# Battery_Monitor_4Cell.net
KiCad netlist of a schematic drawn in Altium Designer
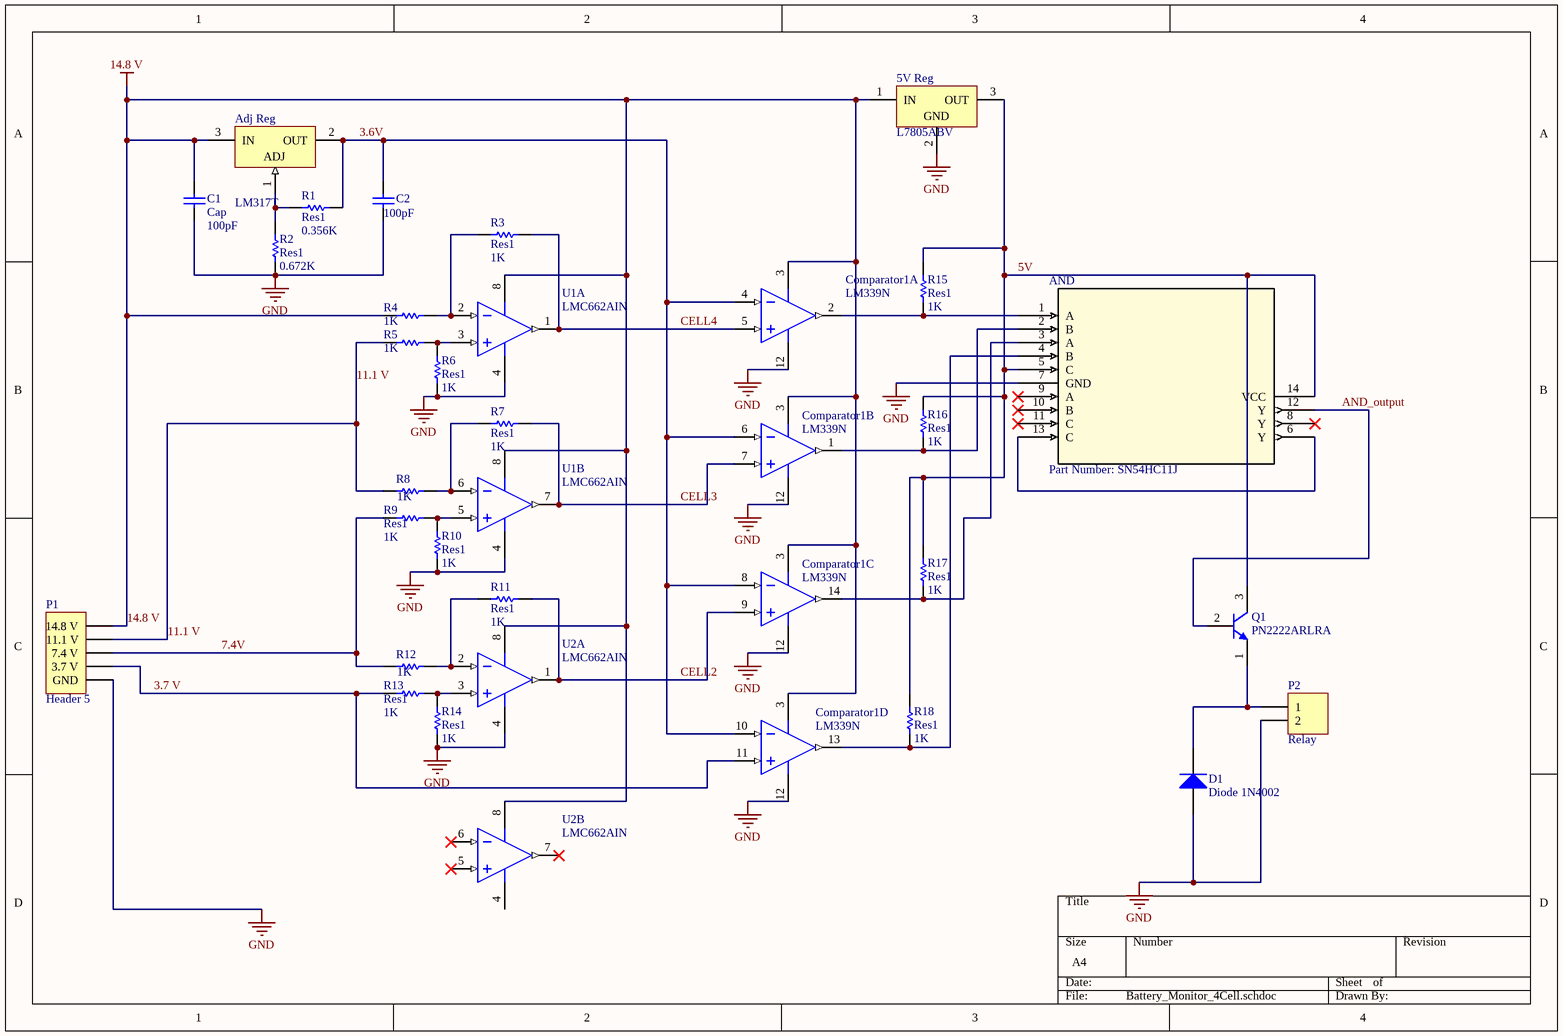
[diagram p0: Battery_Monitor_4Cell.schdoc]

(export (version "E")
  (design (tool "Eeschema 10.0.6"))
  (components
    (comp (ref "5V Reg")
      (value "L7805ABV")
      (footprint "TO220")
      (description "Positive Voltage Regulator, 5V, 3-Pin TO-220")
      (libsource (lib "STMicroelectronics Power Management Linear Regulator") (part "L7805ABV"))
    )
    (comp (ref "Adj Reg")
      (value "LM317T")
      (footprint "TO-220")
      (description "1.5A, 1.2V to 37V Adjustable Voltage Regulator, 3-Pin TO-220")
      (libsource (lib "STMicroelectronics Power Management Linear Regulator") (part "LM317T"))
    )
    (comp (ref "AND")
      (value "Part Number: SN54HC11J")
      (footprint "J14")
      (description "No Description Available")
      (fields
        (field (name "MANUFACTURER_PART_NUMBER") "SN54HC11J")
        (field (name "COPYRIGHT") "Copyright (C) 2018 Accelerated Designs. All rights reserved")
      )
      (libsource (lib "2019-10-26_21-45-44") (part "SN54HC11J"))
    )
    (comp (ref "C1")
      (value "Cap")
      (footprint "RAD-0.3")
      (description "Capacitor")
      (fields (field (name "ALTIUM_VALUE") "100pF") (field (name "PUBLISHER") "Altium Limited"))
      (libsource (lib "Miscellaneous Devices") (part "Cap"))
    )
    (comp (ref "C2")
      (value "100pF")
      (footprint "RAD-0.3")
      (description "Capacitor")
      (fields (field (name "Comment") "Cap") (field (name "PUBLISHER") "Altium Limited"))
      (libsource (lib "Miscellaneous Devices") (part "Cap"))
    )
    (comp (ref "Comparator1")
      (value "LM339N")
      (footprint "N14A")
      (description "Low Power Low Offset Voltage Quad Comparator, 14-pin MDIP")
      (fields (field (name "MANUFACTURER") "National Semiconductor"))
      (libsource (lib "National Semiconductor Amplifier") (part "LM339N"))
    )
    (comp (ref "D1")
      (value "Diode 1N4002")
      (footprint "DO-41")
      (description "1 Amp General Purpose Rectifier")
      (fields (field (name "PUBLISHER") "Altium Limited"))
      (libsource (lib "Miscellaneous Devices") (part "Diode 1N4002"))
    )
    (comp (ref "P1")
      (value "Header 5")
      (footprint "HDR1X5")
      (description "Header, 5-Pin")
      (fields (field (name "PUBLISHER") "Altium Limited"))
      (libsource (lib "Miscellaneous Connectors") (part "Header 5"))
    )
    (comp (ref "P2")
      (value "Relay")
      (footprint "HDR1X2")
      (description "Header, 2-Pin")
      (fields (field (name "PUBLISHER") "Altium Limited"))
      (libsource (lib "Miscellaneous Connectors") (part "Header 2"))
    )
    (comp (ref "Q1")
      (value "PN2222ARLRA")
      (footprint "ONSC-TO-92-3-29-11_AM_BL")
      (description "General Purpose Transistor, NPN Silicon, 3-Pin TO-92, Tape and Reel")
      (fields (field (name "MANUFACTURER") "On Semiconductor"))
      (libsource (lib "ON Semi General Purpose Transistors") (part "PN2222ARLRA"))
    )
    (comp (ref "R1")
      (value "Res1")
      (footprint "AXIAL-0.3")
      (description "Resistor")
      (fields (field (name "ALTIUM_VALUE") "0.356K") (field (name "PUBLISHER") "Altium Limited"))
      (libsource (lib "Miscellaneous Devices") (part "Res1"))
    )
    (comp (ref "R2")
      (value "Res1")
      (footprint "AXIAL-0.3")
      (description "Resistor")
      (fields (field (name "ALTIUM_VALUE") "0.672K") (field (name "PUBLISHER") "Altium Limited"))
      (libsource (lib "Miscellaneous Devices") (part "Res1"))
    )
    (comp (ref "R3")
      (value "Res1")
      (footprint "AXIAL-0.3")
      (description "Resistor")
      (fields (field (name "ALTIUM_VALUE") "1K") (field (name "PUBLISHER") "Altium Limited"))
      (libsource (lib "Miscellaneous Devices") (part "Res1"))
    )
    (comp (ref "R4")
      (value "1K")
      (footprint "AXIAL-0.3")
      (description "Resistor")
      (fields (field (name "Comment") "Res1") (field (name "PUBLISHER") "Altium Limited"))
      (libsource (lib "Miscellaneous Devices") (part "Res1"))
    )
    (comp (ref "R5")
      (value "1K")
      (footprint "AXIAL-0.3")
      (description "Resistor")
      (fields (field (name "Comment") "Res1") (field (name "PUBLISHER") "Altium Limited"))
      (libsource (lib "Miscellaneous Devices") (part "Res1"))
    )
    (comp (ref "R6")
      (value "Res1")
      (footprint "AXIAL-0.3")
      (description "Resistor")
      (fields (field (name "ALTIUM_VALUE") "1K") (field (name "PUBLISHER") "Altium Limited"))
      (libsource (lib "Miscellaneous Devices") (part "Res1"))
    )
    (comp (ref "R7")
      (value "Res1")
      (footprint "AXIAL-0.3")
      (description "Resistor")
      (fields (field (name "ALTIUM_VALUE") "1K") (field (name "PUBLISHER") "Altium Limited"))
      (libsource (lib "Miscellaneous Devices") (part "Res1"))
    )
    (comp (ref "R8")
      (value "1K")
      (footprint "AXIAL-0.3")
      (description "Resistor")
      (fields (field (name "Comment") "Res1") (field (name "PUBLISHER") "Altium Limited"))
      (libsource (lib "Miscellaneous Devices") (part "Res1"))
    )
    (comp (ref "R9")
      (value "Res1")
      (footprint "AXIAL-0.3")
      (description "Resistor")
      (fields (field (name "ALTIUM_VALUE") "1K") (field (name "PUBLISHER") "Altium Limited"))
      (libsource (lib "Miscellaneous Devices") (part "Res1"))
    )
    (comp (ref "R10")
      (value "Res1")
      (footprint "AXIAL-0.3")
      (description "Resistor")
      (fields (field (name "ALTIUM_VALUE") "1K") (field (name "PUBLISHER") "Altium Limited"))
      (libsource (lib "Miscellaneous Devices") (part "Res1"))
    )
    (comp (ref "R11")
      (value "Res1")
      (footprint "AXIAL-0.3")
      (description "Resistor")
      (fields (field (name "ALTIUM_VALUE") "1K") (field (name "PUBLISHER") "Altium Limited"))
      (libsource (lib "Miscellaneous Devices") (part "Res1"))
    )
    (comp (ref "R12")
      (value "1K")
      (footprint "AXIAL-0.3")
      (description "Resistor")
      (fields (field (name "Comment") "Res1") (field (name "PUBLISHER") "Altium Limited"))
      (libsource (lib "Miscellaneous Devices") (part "Res1"))
    )
    (comp (ref "R13")
      (value "Res1")
      (footprint "AXIAL-0.3")
      (description "Resistor")
      (fields (field (name "ALTIUM_VALUE") "1K") (field (name "PUBLISHER") "Altium Limited"))
      (libsource (lib "Miscellaneous Devices") (part "Res1"))
    )
    (comp (ref "R14")
      (value "Res1")
      (footprint "AXIAL-0.3")
      (description "Resistor")
      (fields (field (name "ALTIUM_VALUE") "1K") (field (name "PUBLISHER") "Altium Limited"))
      (libsource (lib "Miscellaneous Devices") (part "Res1"))
    )
    (comp (ref "R15")
      (value "Res1")
      (footprint "AXIAL-0.3")
      (description "Resistor")
      (fields (field (name "ALTIUM_VALUE") "1K") (field (name "PUBLISHER") "Altium Limited"))
      (libsource (lib "Miscellaneous Devices") (part "Res1"))
    )
    (comp (ref "R16")
      (value "Res1")
      (footprint "AXIAL-0.3")
      (description "Resistor")
      (fields (field (name "ALTIUM_VALUE") "1K") (field (name "PUBLISHER") "Altium Limited"))
      (libsource (lib "Miscellaneous Devices") (part "Res1"))
    )
    (comp (ref "R17")
      (value "Res1")
      (footprint "AXIAL-0.3")
      (description "Resistor")
      (fields (field (name "ALTIUM_VALUE") "1K") (field (name "PUBLISHER") "Altium Limited"))
      (libsource (lib "Miscellaneous Devices") (part "Res1"))
    )
    (comp (ref "R18")
      (value "Res1")
      (footprint "AXIAL-0.3")
      (description "Resistor")
      (fields (field (name "ALTIUM_VALUE") "1K") (field (name "PUBLISHER") "Altium Limited"))
      (libsource (lib "Miscellaneous Devices") (part "Res1"))
    )
    (comp (ref "U1")
      (value "LMC662AIN")
      (footprint "N08E")
      (description "CMOS Dual Operational Amplifier, 8-pin MDIP")
      (fields (field (name "MANUFACTURER") "National Semiconductor"))
      (libsource (lib "National Semiconductor Amplifier") (part "LMC662AIN"))
    )
    (comp (ref "U2")
      (value "LMC662AIN")
      (footprint "N08E")
      (description "CMOS Dual Operational Amplifier, 8-pin MDIP")
      (fields (field (name "MANUFACTURER") "National Semiconductor"))
      (libsource (lib "National Semiconductor Amplifier") (part "LMC662AIN"))
    )
  )
  (nets
    (net (code "1") (name "/3.6V") (class "Default")
      (node (ref "Adj Reg") (pin "2") (pinfunction "OUT_2") (pintype "power_in"))
      (node (ref "C2") (pin "1") (pinfunction "1_1") (pintype "passive"))
      (node (ref "Comparator1") (pin "10") (pinfunction "IN4-_10") (pintype "input"))
      (node (ref "Comparator1") (pin "4") (pinfunction "IN1-_4") (pintype "input"))
      (node (ref "Comparator1") (pin "6") (pinfunction "IN2-_6") (pintype "input"))
      (node (ref "Comparator1") (pin "8") (pinfunction "IN3-_8") (pintype "input"))
      (node (ref "R1") (pin "2") (pinfunction "2_2") (pintype "passive"))
    )
    (net (code "2") (name "/3.7 V") (class "Default")
      (node (ref "Comparator1") (pin "11") (pinfunction "IN4+_11") (pintype "input"))
      (node (ref "P1") (pin "2") (pinfunction "3.7_V_2") (pintype "passive"))
      (node (ref "R13") (pin "1") (pinfunction "1_1") (pintype "passive"))
    )
    (net (code "3") (name "/5V") (class "Default")
      (node (ref "5V Reg") (pin "3") (pinfunction "OUT_3") (pintype "power_in"))
      (node (ref "AND") (pin "14") (pinfunction "VCC_14") (pintype "power_in"))
      (node (ref "AND") (pin "5") (pinfunction "C_5") (pintype "input"))
      (node (ref "Q1") (pin "3") (pinfunction "C_3") (pintype "passive"))
      (node (ref "R15") (pin "2") (pinfunction "2_2") (pintype "passive"))
      (node (ref "R16") (pin "2") (pinfunction "2_2") (pintype "passive"))
      (node (ref "R17") (pin "2") (pinfunction "2_2") (pintype "passive"))
      (node (ref "R18") (pin "2") (pinfunction "2_2") (pintype "passive"))
    )
    (net (code "4") (name "/7.4V") (class "Default")
      (node (ref "P1") (pin "3") (pinfunction "7.4_V_3") (pintype "passive"))
      (node (ref "R12") (pin "1") (pinfunction "1_1") (pintype "passive"))
      (node (ref "R9") (pin "1") (pinfunction "1_1") (pintype "passive"))
    )
    (net (code "5") (name "/11.1 V") (class "Default")
      (node (ref "P1") (pin "4") (pinfunction "11.1_V_4") (pintype "passive"))
      (node (ref "R5") (pin "1") (pinfunction "1_1") (pintype "passive"))
      (node (ref "R8") (pin "1") (pinfunction "1_1") (pintype "passive"))
    )
    (net (code "6") (name "/AND_output") (class "Default")
      (node (ref "AND") (pin "12") (pinfunction "Y_12") (pintype "output"))
      (node (ref "Q1") (pin "2") (pinfunction "B_2") (pintype "passive"))
    )
    (net (code "7") (name "/CELL2") (class "Default")
      (node (ref "Comparator1") (pin "9") (pinfunction "IN3+_9") (pintype "input"))
      (node (ref "R11") (pin "2") (pinfunction "2_2") (pintype "passive"))
      (node (ref "U2") (pin "1") (pinfunction "OUTA_1") (pintype "output"))
    )
    (net (code "8") (name "/CELL3") (class "Default")
      (node (ref "Comparator1") (pin "7") (pinfunction "IN2+_7") (pintype "input"))
      (node (ref "R7") (pin "2") (pinfunction "2_2") (pintype "passive"))
      (node (ref "U1") (pin "7") (pinfunction "OUTB_7") (pintype "output"))
    )
    (net (code "9") (name "/CELL4") (class "Default")
      (node (ref "Comparator1") (pin "5") (pinfunction "IN1+_5") (pintype "input"))
      (node (ref "R3") (pin "2") (pinfunction "2_2") (pintype "passive"))
      (node (ref "U1") (pin "1") (pinfunction "OUTA_1") (pintype "output"))
    )
    (net (code "10") (name "14.8 V") (class "Default")
      (node (ref "5V Reg") (pin "1") (pinfunction "IN_1") (pintype "power_in"))
      (node (ref "Adj Reg") (pin "3") (pinfunction "IN_3") (pintype "power_in"))
      (node (ref "C1") (pin "2") (pinfunction "2_2") (pintype "passive"))
      (node (ref "Comparator1") (pin "3") (pinfunction "V+_3") (pintype "power_in"))
      (node (ref "P1") (pin "5") (pinfunction "14.8_V_5") (pintype "passive"))
      (node (ref "R4") (pin "1") (pinfunction "1_1") (pintype "passive"))
      (node (ref "U1") (pin "8") (pinfunction "V+_8") (pintype "power_in"))
      (node (ref "U2") (pin "8") (pinfunction "V+_8") (pintype "power_in"))
    )
    (net (code "11") (name "GND") (class "Default")
      (node (ref "5V Reg") (pin "2") (pinfunction "GND_2") (pintype "power_in"))
      (node (ref "AND") (pin "7") (pinfunction "GND_7") (pintype "power_in"))
      (node (ref "C1") (pin "1") (pinfunction "1_1") (pintype "passive"))
      (node (ref "C2") (pin "2") (pinfunction "2_2") (pintype "passive"))
      (node (ref "Comparator1") (pin "12") (pinfunction "GND_12") (pintype "power_in"))
      (node (ref "D1") (pin "1") (pinfunction "A_1") (pintype "passive"))
      (node (ref "P1") (pin "1") (pinfunction "GND_1") (pintype "passive"))
      (node (ref "P2") (pin "2") (pinfunction "2_2") (pintype "passive"))
      (node (ref "R10") (pin "1") (pinfunction "1_1") (pintype "passive"))
      (node (ref "R14") (pin "1") (pinfunction "1_1") (pintype "passive"))
      (node (ref "R2") (pin "1") (pinfunction "1_1") (pintype "passive"))
      (node (ref "R6") (pin "1") (pinfunction "1_1") (pintype "passive"))
      (node (ref "U1") (pin "4") (pinfunction "V-_4") (pintype "power_in"))
      (node (ref "U2") (pin "4") (pinfunction "V-_4") (pintype "power_in"))
    )
    (net (code "12") (name "Net-(AND-C-Pad13)") (class "Default")
      (node (ref "AND") (pin "13") (pinfunction "C_13") (pintype "input"))
      (node (ref "AND") (pin "6") (pinfunction "Y_6") (pintype "output"))
    )
    (net (code "13") (name "Net-(Adj Reg-ADJ)") (class "Default")
      (node (ref "Adj Reg") (pin "1") (pinfunction "ADJ_1") (pintype "input"))
      (node (ref "R1") (pin "1") (pinfunction "1_1") (pintype "passive"))
      (node (ref "R2") (pin "2") (pinfunction "2_2") (pintype "passive"))
    )
    (net (code "14") (name "Net-(Comparator1A-OUT1)") (class "Default")
      (node (ref "AND") (pin "1") (pinfunction "A_1") (pintype "input"))
      (node (ref "Comparator1") (pin "2") (pinfunction "OUT1_2") (pintype "output"))
      (node (ref "R15") (pin "1") (pinfunction "1_1") (pintype "passive"))
    )
    (net (code "15") (name "Net-(Comparator1B-OUT2)") (class "Default")
      (node (ref "AND") (pin "2") (pinfunction "B_2") (pintype "input"))
      (node (ref "Comparator1") (pin "1") (pinfunction "OUT2_1") (pintype "output"))
      (node (ref "R16") (pin "1") (pinfunction "1_1") (pintype "passive"))
    )
    (net (code "16") (name "Net-(Comparator1C-OUT3)") (class "Default")
      (node (ref "AND") (pin "3") (pinfunction "A_3") (pintype "input"))
      (node (ref "Comparator1") (pin "14") (pinfunction "OUT3_14") (pintype "output"))
      (node (ref "R17") (pin "1") (pinfunction "1_1") (pintype "passive"))
    )
    (net (code "17") (name "Net-(Comparator1D-OUT4)") (class "Default")
      (node (ref "AND") (pin "4") (pinfunction "B_4") (pintype "input"))
      (node (ref "Comparator1") (pin "13") (pinfunction "OUT4_13") (pintype "output"))
      (node (ref "R18") (pin "1") (pinfunction "1_1") (pintype "passive"))
    )
    (net (code "18") (name "Net-(D1-K)") (class "Default")
      (node (ref "D1") (pin "2") (pinfunction "K_2") (pintype "passive"))
      (node (ref "P2") (pin "1") (pinfunction "1_1") (pintype "passive"))
      (node (ref "Q1") (pin "1") (pinfunction "E_1") (pintype "passive"))
    )
    (net (code "19") (name "Net-(U1A-INA+)") (class "Default")
      (node (ref "R5") (pin "2") (pinfunction "2_2") (pintype "passive"))
      (node (ref "R6") (pin "2") (pinfunction "2_2") (pintype "passive"))
      (node (ref "U1") (pin "3") (pinfunction "INA+_3") (pintype "input"))
    )
    (net (code "20") (name "Net-(U1A-INA-)") (class "Default")
      (node (ref "R3") (pin "1") (pinfunction "1_1") (pintype "passive"))
      (node (ref "R4") (pin "2") (pinfunction "2_2") (pintype "passive"))
      (node (ref "U1") (pin "2") (pinfunction "INA-_2") (pintype "input"))
    )
    (net (code "21") (name "Net-(U1B-INB+)") (class "Default")
      (node (ref "R10") (pin "2") (pinfunction "2_2") (pintype "passive"))
      (node (ref "R9") (pin "2") (pinfunction "2_2") (pintype "passive"))
      (node (ref "U1") (pin "5") (pinfunction "INB+_5") (pintype "input"))
    )
    (net (code "22") (name "Net-(U1B-INB-)") (class "Default")
      (node (ref "R7") (pin "1") (pinfunction "1_1") (pintype "passive"))
      (node (ref "R8") (pin "2") (pinfunction "2_2") (pintype "passive"))
      (node (ref "U1") (pin "6") (pinfunction "INB-_6") (pintype "input"))
    )
    (net (code "23") (name "Net-(U2A-INA+)") (class "Default")
      (node (ref "R13") (pin "2") (pinfunction "2_2") (pintype "passive"))
      (node (ref "R14") (pin "2") (pinfunction "2_2") (pintype "passive"))
      (node (ref "U2") (pin "3") (pinfunction "INA+_3") (pintype "input"))
    )
    (net (code "24") (name "Net-(U2A-INA-)") (class "Default")
      (node (ref "R11") (pin "1") (pinfunction "1_1") (pintype "passive"))
      (node (ref "R12") (pin "2") (pinfunction "2_2") (pintype "passive"))
      (node (ref "U2") (pin "2") (pinfunction "INA-_2") (pintype "input"))
    )
    (net (code "25") (name "unconnected-(AND-A-Pad9)") (class "Default")
      (node (ref "AND") (pin "9") (pinfunction "A_9") (pintype "input+no_connect"))
    )
    (net (code "26") (name "unconnected-(AND-B-Pad10)") (class "Default")
      (node (ref "AND") (pin "10") (pinfunction "B_10") (pintype "input+no_connect"))
    )
    (net (code "27") (name "unconnected-(AND-C-Pad11)") (class "Default")
      (node (ref "AND") (pin "11") (pinfunction "C_11") (pintype "input+no_connect"))
    )
    (net (code "28") (name "unconnected-(AND-Y-Pad8)") (class "Default")
      (node (ref "AND") (pin "8") (pinfunction "Y_8") (pintype "output+no_connect"))
    )
    (net (code "29") (name "unconnected-(U2B-INB+-Pad5)") (class "Default")
      (node (ref "U2") (pin "5") (pinfunction "INB+_5") (pintype "input+no_connect"))
    )
    (net (code "30") (name "unconnected-(U2B-INB--Pad6)") (class "Default")
      (node (ref "U2") (pin "6") (pinfunction "INB-_6") (pintype "input+no_connect"))
    )
    (net (code "31") (name "unconnected-(U2B-OUTB-Pad7)") (class "Default")
      (node (ref "U2") (pin "7") (pinfunction "OUTB_7") (pintype "output+no_connect"))
    )
    (net (code "32") (name "unconnected-(U2B-V--Pad4)") (class "Default")
      (node (ref "U2") (pin "4") (pinfunction "V-_4") (pintype "power_in"))
    )
  )
)
